# irRemoteLEDs.net
KiCad netlist of a schematic drawn in EAGLE
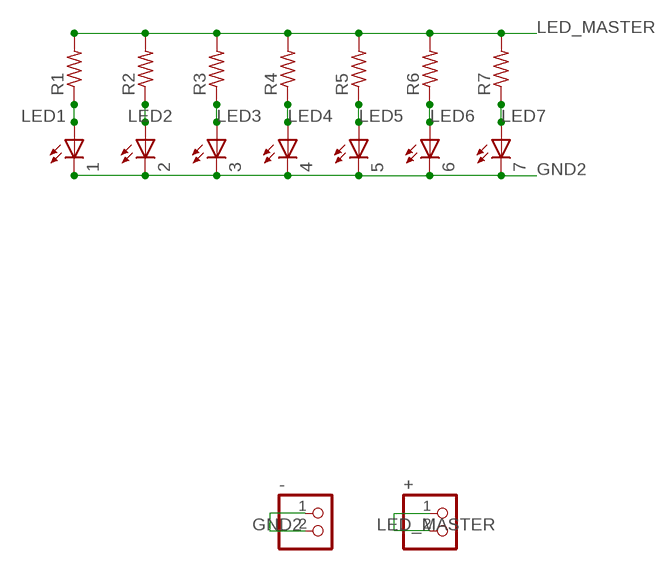
[diagram p0: schematic, sheet 1]

(export (version "E")
  (design (tool "Eeschema 10.0.6"))
  (components
    (comp (ref "+")
      (value "PINHD-1X2")
      (footprint "eagle-import:1X02")
      (libsource (lib "eagle-import") (part "PINHD-1X2"))
    )
    (comp (ref "-")
      (value "PINHD-1X2")
      (footprint "eagle-import:1X02")
      (libsource (lib "eagle-import") (part "PINHD-1X2"))
    )
    (comp (ref "1")
      (value "LED5MM")
      (footprint "eagle-import:LED5MM")
      (libsource (lib "eagle-import") (part "LED5MM"))
    )
    (comp (ref "2")
      (value "LED5MM")
      (footprint "eagle-import:LED5MM")
      (libsource (lib "eagle-import") (part "LED5MM"))
    )
    (comp (ref "3")
      (value "LED5MM")
      (footprint "eagle-import:LED5MM")
      (libsource (lib "eagle-import") (part "LED5MM"))
    )
    (comp (ref "4")
      (value "LED5MM")
      (footprint "eagle-import:LED5MM")
      (libsource (lib "eagle-import") (part "LED5MM"))
    )
    (comp (ref "5")
      (value "LED5MM")
      (footprint "eagle-import:LED5MM")
      (libsource (lib "eagle-import") (part "LED5MM"))
    )
    (comp (ref "6")
      (value "LED5MM")
      (footprint "eagle-import:LED5MM")
      (libsource (lib "eagle-import") (part "LED5MM"))
    )
    (comp (ref "7")
      (value "LED5MM")
      (footprint "eagle-import:LED5MM")
      (libsource (lib "eagle-import") (part "LED5MM"))
    )
    (comp (ref "R1")
      (value "R-US_M0805")
      (footprint "eagle-import:M0805")
      (libsource (lib "eagle-import") (part "R-US_M0805"))
    )
    (comp (ref "R2")
      (value "R-US_M0805")
      (footprint "eagle-import:M0805")
      (libsource (lib "eagle-import") (part "R-US_M0805"))
    )
    (comp (ref "R3")
      (value "R-US_M0805")
      (footprint "eagle-import:M0805")
      (libsource (lib "eagle-import") (part "R-US_M0805"))
    )
    (comp (ref "R4")
      (value "R-US_M0805")
      (footprint "eagle-import:M0805")
      (libsource (lib "eagle-import") (part "R-US_M0805"))
    )
    (comp (ref "R5")
      (value "R-US_M0805")
      (footprint "eagle-import:M0805")
      (libsource (lib "eagle-import") (part "R-US_M0805"))
    )
    (comp (ref "R6")
      (value "R-US_M0805")
      (footprint "eagle-import:M0805")
      (libsource (lib "eagle-import") (part "R-US_M0805"))
    )
    (comp (ref "R7")
      (value "R-US_M0805")
      (footprint "eagle-import:M0805")
      (libsource (lib "eagle-import") (part "R-US_M0805"))
    )
  )
  (nets
    (net (code "1") (name "/GND2") (class "Default")
      (node (ref "-") (pin "1") (pinfunction "1_1") (pintype "passive"))
      (node (ref "-") (pin "2") (pinfunction "2_2") (pintype "passive"))
      (node (ref "1") (pin "K") (pinfunction "C_K") (pintype "passive"))
      (node (ref "2") (pin "K") (pinfunction "C_K") (pintype "passive"))
      (node (ref "3") (pin "K") (pinfunction "C_K") (pintype "passive"))
      (node (ref "4") (pin "K") (pinfunction "C_K") (pintype "passive"))
      (node (ref "5") (pin "K") (pinfunction "C_K") (pintype "passive"))
      (node (ref "6") (pin "K") (pinfunction "C_K") (pintype "passive"))
      (node (ref "7") (pin "K") (pinfunction "C_K") (pintype "passive"))
    )
    (net (code "2") (name "/LED1") (class "Default")
      (node (ref "1") (pin "A") (pinfunction "A_A") (pintype "passive"))
      (node (ref "R1") (pin "1") (pinfunction "1_1") (pintype "passive"))
    )
    (net (code "3") (name "/LED2") (class "Default")
      (node (ref "2") (pin "A") (pinfunction "A_A") (pintype "passive"))
      (node (ref "R2") (pin "1") (pinfunction "1_1") (pintype "passive"))
    )
    (net (code "4") (name "/LED3") (class "Default")
      (node (ref "3") (pin "A") (pinfunction "A_A") (pintype "passive"))
      (node (ref "R3") (pin "1") (pinfunction "1_1") (pintype "passive"))
    )
    (net (code "5") (name "/LED4") (class "Default")
      (node (ref "4") (pin "A") (pinfunction "A_A") (pintype "passive"))
      (node (ref "R4") (pin "1") (pinfunction "1_1") (pintype "passive"))
    )
    (net (code "6") (name "/LED5") (class "Default")
      (node (ref "5") (pin "A") (pinfunction "A_A") (pintype "passive"))
      (node (ref "R5") (pin "1") (pinfunction "1_1") (pintype "passive"))
    )
    (net (code "7") (name "/LED6") (class "Default")
      (node (ref "6") (pin "A") (pinfunction "A_A") (pintype "passive"))
      (node (ref "R6") (pin "1") (pinfunction "1_1") (pintype "passive"))
    )
    (net (code "8") (name "/LED7") (class "Default")
      (node (ref "7") (pin "A") (pinfunction "A_A") (pintype "passive"))
      (node (ref "R7") (pin "1") (pinfunction "1_1") (pintype "passive"))
    )
    (net (code "9") (name "/LED_MASTER") (class "Default")
      (node (ref "+") (pin "1") (pinfunction "1_1") (pintype "passive"))
      (node (ref "+") (pin "2") (pinfunction "2_2") (pintype "passive"))
      (node (ref "R1") (pin "2") (pinfunction "2_2") (pintype "passive"))
      (node (ref "R2") (pin "2") (pinfunction "2_2") (pintype "passive"))
      (node (ref "R3") (pin "2") (pinfunction "2_2") (pintype "passive"))
      (node (ref "R4") (pin "2") (pinfunction "2_2") (pintype "passive"))
      (node (ref "R5") (pin "2") (pinfunction "2_2") (pintype "passive"))
      (node (ref "R6") (pin "2") (pinfunction "2_2") (pintype "passive"))
      (node (ref "R7") (pin "2") (pinfunction "2_2") (pintype "passive"))
    )
  )
)
